# DWM3000TR13.net
KiCad netlist of a schematic drawn in Altium Designer
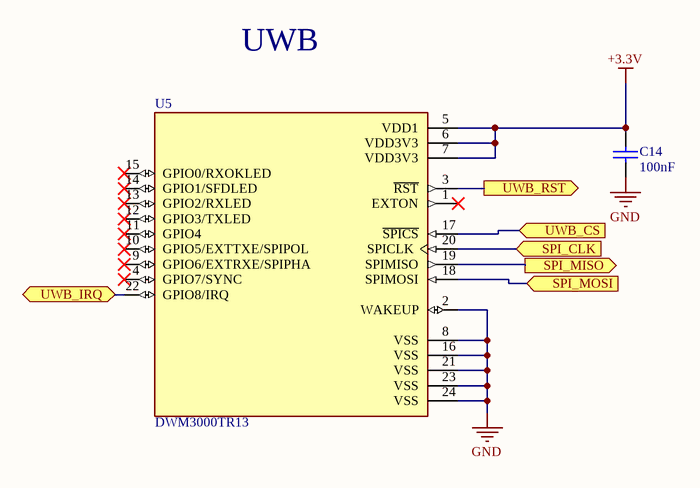
[diagram p0: DWM3000TR13.SchDoc]

(export (version "E")
  (design (tool "Eeschema 10.0.6"))
  (components
    (comp (ref "C14")
      (value "100nF")
      (footprint "CAPC1005X55N")
      (description "Capacitor")
      (fields (field (name "Comment") "Cap") (field (name "PUBLISHER") "Altium Limited"))
      (libsource (lib "Miscellaneous Devices") (part "Cap"))
    )
    (comp (ref "U5")
      (value "DWM3000TR13")
      (footprint "XCVR_DWM3000TR13")
      (fields (field (name "MF") "Qorvo"))
      (libsource (lib "DWM3000TR13") (part "DWM3000TR13"))
    )
  )
  (nets
    (net (code "1") (name "+3.3V") (class "Default")
      (node (ref "C14") (pin "2") (pinfunction "2_2") (pintype "passive"))
      (node (ref "U5") (pin "5") (pinfunction "VDD1_5") (pintype "power_in"))
      (node (ref "U5") (pin "6") (pinfunction "VDD3V3_6") (pintype "power_in"))
      (node (ref "U5") (pin "7") (pinfunction "VDD3V3_7") (pintype "power_in"))
    )
    (net (code "2") (name "/SPI_CLK") (class "Default")
      (node (ref "U5") (pin "20") (pinfunction "SPICLK_20") (pintype "input"))
    )
    (net (code "3") (name "/SPI_MISO") (class "Default")
      (node (ref "U5") (pin "19") (pinfunction "SPIMISO_19") (pintype "output"))
    )
    (net (code "4") (name "/SPI_MOSI") (class "Default")
      (node (ref "U5") (pin "18") (pinfunction "SPIMOSI_18") (pintype "input"))
    )
    (net (code "5") (name "/UWB_CS") (class "Default")
      (node (ref "U5") (pin "17") (pinfunction "~{SPICS}_17") (pintype "input"))
    )
    (net (code "6") (name "/UWB_IRQ") (class "Default")
      (node (ref "U5") (pin "22") (pinfunction "GPIO8/IRQ_22") (pintype "bidirectional"))
    )
    (net (code "7") (name "/UWB_RST") (class "Default")
      (node (ref "U5") (pin "3") (pinfunction "~{RST}_3") (pintype "output"))
    )
    (net (code "8") (name "GND") (class "Default")
      (node (ref "C14") (pin "1") (pinfunction "1_1") (pintype "passive"))
      (node (ref "U5") (pin "16") (pinfunction "VSS_16") (pintype "power_in"))
      (node (ref "U5") (pin "2") (pinfunction "WAKEUP_2") (pintype "bidirectional"))
      (node (ref "U5") (pin "21") (pinfunction "VSS_21") (pintype "power_in"))
      (node (ref "U5") (pin "23") (pinfunction "VSS_23") (pintype "power_in"))
      (node (ref "U5") (pin "24") (pinfunction "VSS_24") (pintype "power_in"))
      (node (ref "U5") (pin "8") (pinfunction "VSS_8") (pintype "power_in"))
    )
    (net (code "9") (name "unconnected-(U5-EXTON-Pad1)") (class "Default")
      (node (ref "U5") (pin "1") (pinfunction "EXTON_1") (pintype "output+no_connect"))
    )
    (net (code "10") (name "unconnected-(U5-GPIO0{slash}RXOKLED-Pad15)") (class "Default")
      (node (ref "U5") (pin "15") (pinfunction "GPIO0/RXOKLED_15") (pintype "bidirectional+no_connect"))
    )
    (net (code "11") (name "unconnected-(U5-GPIO1{slash}SFDLED-Pad14)") (class "Default")
      (node (ref "U5") (pin "14") (pinfunction "GPIO1/SFDLED_14") (pintype "bidirectional+no_connect"))
    )
    (net (code "12") (name "unconnected-(U5-GPIO2{slash}RXLED-Pad13)") (class "Default")
      (node (ref "U5") (pin "13") (pinfunction "GPIO2/RXLED_13") (pintype "bidirectional+no_connect"))
    )
    (net (code "13") (name "unconnected-(U5-GPIO3{slash}TXLED-Pad12)") (class "Default")
      (node (ref "U5") (pin "12") (pinfunction "GPIO3/TXLED_12") (pintype "bidirectional+no_connect"))
    )
    (net (code "14") (name "unconnected-(U5-GPIO4-Pad11)") (class "Default")
      (node (ref "U5") (pin "11") (pinfunction "GPIO4_11") (pintype "bidirectional+no_connect"))
    )
    (net (code "15") (name "unconnected-(U5-GPIO5{slash}EXTTXE{slash}SPIPOL-Pad10)") (class "Default")
      (node (ref "U5") (pin "10") (pinfunction "GPIO5/EXTTXE/SPIPOL_10") (pintype "bidirectional+no_connect"))
    )
    (net (code "16") (name "unconnected-(U5-GPIO6{slash}EXTRXE{slash}SPIPHA-Pad9)") (class "Default")
      (node (ref "U5") (pin "9") (pinfunction "GPIO6/EXTRXE/SPIPHA_9") (pintype "bidirectional+no_connect"))
    )
    (net (code "17") (name "unconnected-(U5-GPIO7{slash}SYNC-Pad4)") (class "Default")
      (node (ref "U5") (pin "4") (pinfunction "GPIO7/SYNC_4") (pintype "bidirectional+no_connect"))
    )
  )
)
